# ADC_Sheet.net
KiCad netlist of a schematic drawn in Altium Designer
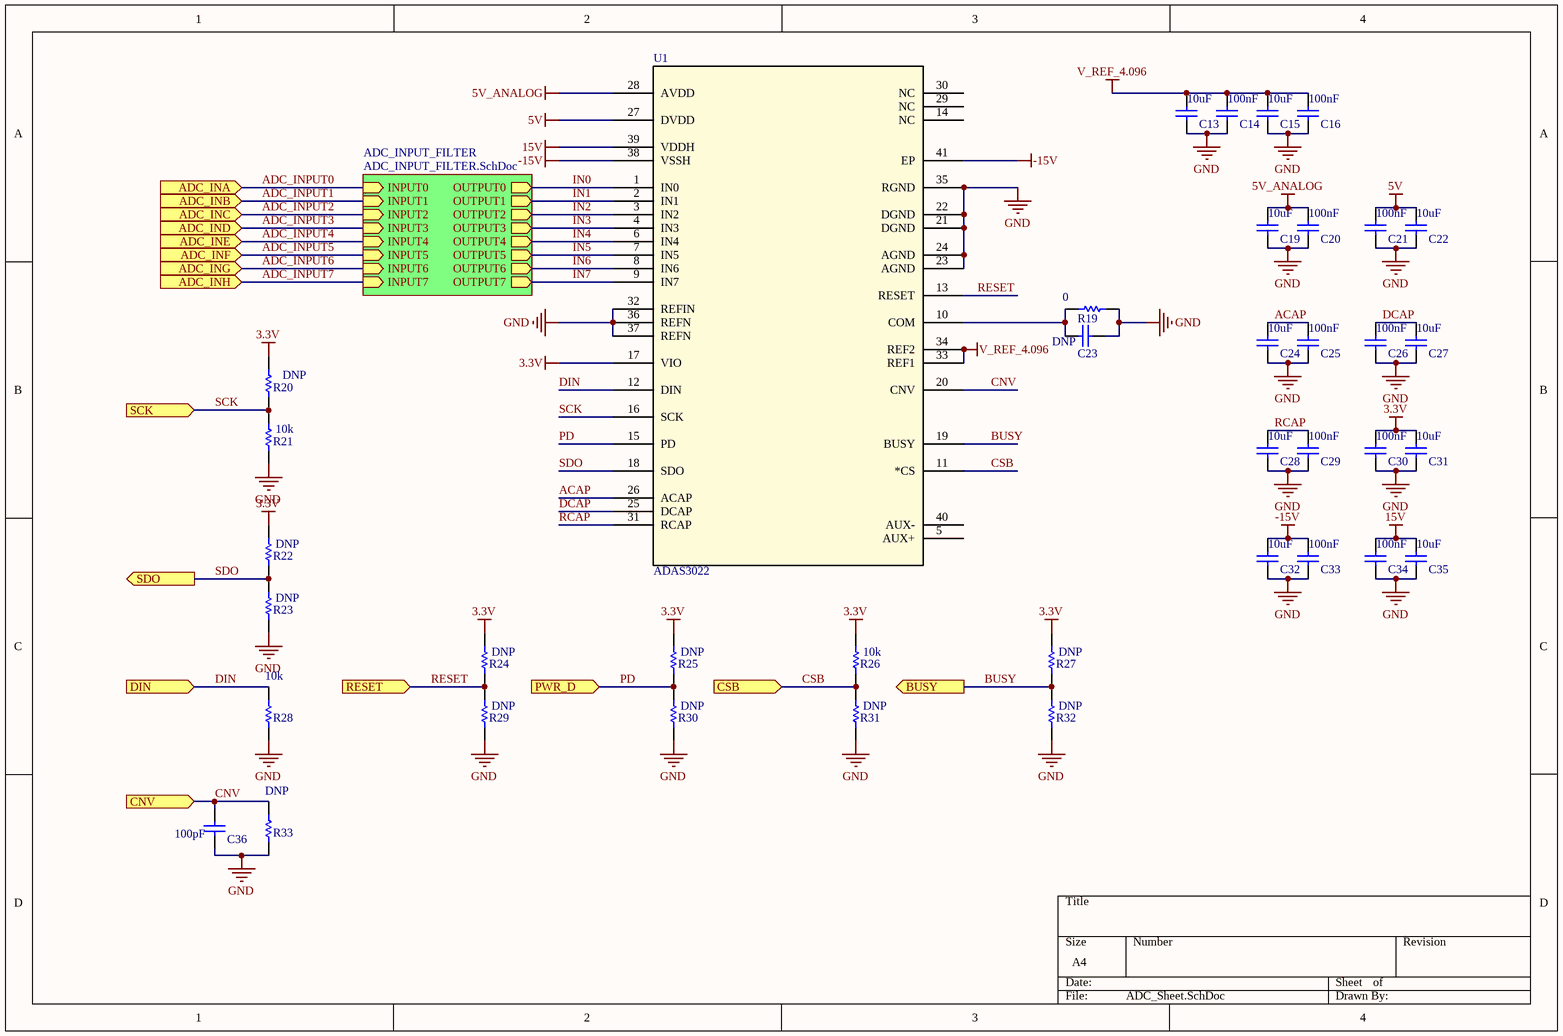
[diagram p0: ADC_Sheet.SchDoc]

(export (version "E")
  (design (tool "Eeschema 10.0.6"))
  (components
    (comp (ref "C13")
      (value "10uF")
      (footprint "CAPC0805(2012)145_L")
      (description "0805 (2012 Metric) Chip Capacitor")
      (fields (field (name "Comment") "CAP0805"))
      (libsource (lib "Altium Content Vault") (part "CMP-1590-00003-1"))
    )
    (comp (ref "C14")
      (value "100nF")
      (footprint "CAPC0402(1005)60_L")
      (description "0402 (1005 Metric) Chip Capacitor")
      (fields (field (name "Comment") "CAP0402"))
      (libsource (lib "Altium Content Vault") (part "CMP-1590-00004-1"))
    )
    (comp (ref "C15")
      (value "10uF")
      (footprint "CAPC0805(2012)145_L")
      (description "0805 (2012 Metric) Chip Capacitor")
      (fields (field (name "Comment") "CAP0805"))
      (libsource (lib "Altium Content Vault") (part "CMP-1590-00003-1"))
    )
    (comp (ref "C16")
      (value "100nF")
      (footprint "CAPC0402(1005)60_L")
      (description "0402 (1005 Metric) Chip Capacitor")
      (fields (field (name "Comment") "CAP0402"))
      (libsource (lib "Altium Content Vault") (part "CMP-1590-00004-1"))
    )
    (comp (ref "C19")
      (value "10uF")
      (footprint "CAPC0805(2012)145_L")
      (description "0805 (2012 Metric) Chip Capacitor")
      (fields (field (name "Comment") "CAP0805"))
      (libsource (lib "Altium Content Vault") (part "CMP-1590-00003-1"))
    )
    (comp (ref "C20")
      (value "100nF")
      (footprint "CAPC0402(1005)60_L")
      (description "0402 (1005 Metric) Chip Capacitor")
      (fields (field (name "Comment") "CAP0402"))
      (libsource (lib "Altium Content Vault") (part "CMP-1590-00004-1"))
    )
    (comp (ref "C21")
      (value "100nF")
      (footprint "CAPC0402(1005)60_L")
      (description "0402 (1005 Metric) Chip Capacitor")
      (fields (field (name "Comment") "CAP0402"))
      (libsource (lib "Altium Content Vault") (part "CMP-1590-00004-1"))
    )
    (comp (ref "C22")
      (value "10uF")
      (footprint "CAPC0805(2012)145_L")
      (description "0805 (2012 Metric) Chip Capacitor")
      (fields (field (name "Comment") "CAP0805"))
      (libsource (lib "Altium Content Vault") (part "CMP-1590-00003-1"))
    )
    (comp (ref "C23")
      (value "DNP")
      (footprint "CAPC0402(1005)60_L")
      (description "0402 (1005 Metric) Chip Capacitor")
      (fields (field (name "Comment") "CAP0402"))
      (libsource (lib "Altium Content Vault") (part "CMP-1590-00004-1"))
    )
    (comp (ref "C24")
      (value "10uF")
      (footprint "CAPC0805(2012)145_L")
      (description "0805 (2012 Metric) Chip Capacitor")
      (fields (field (name "Comment") "CAP0805"))
      (libsource (lib "Altium Content Vault") (part "CMP-1590-00003-1"))
    )
    (comp (ref "C25")
      (value "100nF")
      (footprint "CAPC0402(1005)60_L")
      (description "0402 (1005 Metric) Chip Capacitor")
      (fields (field (name "Comment") "CAP0402"))
      (libsource (lib "Altium Content Vault") (part "CMP-1590-00004-1"))
    )
    (comp (ref "C26")
      (value "100nF")
      (footprint "CAPC0402(1005)60_L")
      (description "0402 (1005 Metric) Chip Capacitor")
      (fields (field (name "Comment") "CAP0402"))
      (libsource (lib "Altium Content Vault") (part "CMP-1590-00004-1"))
    )
    (comp (ref "C27")
      (value "10uF")
      (footprint "CAPC0805(2012)145_L")
      (description "0805 (2012 Metric) Chip Capacitor")
      (fields (field (name "Comment") "CAP0805"))
      (libsource (lib "Altium Content Vault") (part "CMP-1590-00003-1"))
    )
    (comp (ref "C28")
      (value "10uF")
      (footprint "CAPC0805(2012)145_L")
      (description "0805 (2012 Metric) Chip Capacitor")
      (fields (field (name "Comment") "CAP0805"))
      (libsource (lib "Altium Content Vault") (part "CMP-1590-00003-1"))
    )
    (comp (ref "C29")
      (value "100nF")
      (footprint "CAPC0402(1005)60_L")
      (description "0402 (1005 Metric) Chip Capacitor")
      (fields (field (name "Comment") "CAP0402"))
      (libsource (lib "Altium Content Vault") (part "CMP-1590-00004-1"))
    )
    (comp (ref "C30")
      (value "100nF")
      (footprint "CAPC0402(1005)60_L")
      (description "0402 (1005 Metric) Chip Capacitor")
      (fields (field (name "Comment") "CAP0402"))
      (libsource (lib "Altium Content Vault") (part "CMP-1590-00004-1"))
    )
    (comp (ref "C31")
      (value "10uF")
      (footprint "CAPC0805(2012)145_L")
      (description "0805 (2012 Metric) Chip Capacitor")
      (fields (field (name "Comment") "CAP0805"))
      (libsource (lib "Altium Content Vault") (part "CMP-1590-00003-1"))
    )
    (comp (ref "C32")
      (value "10uF")
      (footprint "CAPC0805(2012)145_L")
      (description "0805 (2012 Metric) Chip Capacitor")
      (fields (field (name "Comment") "CAP0805"))
      (libsource (lib "Altium Content Vault") (part "CMP-1590-00003-1"))
    )
    (comp (ref "C33")
      (value "100nF")
      (footprint "CAPC0402(1005)60_L")
      (description "0402 (1005 Metric) Chip Capacitor")
      (fields (field (name "Comment") "CAP0402"))
      (libsource (lib "Altium Content Vault") (part "CMP-1590-00004-1"))
    )
    (comp (ref "C34")
      (value "100nF")
      (footprint "CAPC0402(1005)60_L")
      (description "0402 (1005 Metric) Chip Capacitor")
      (fields (field (name "Comment") "CAP0402"))
      (libsource (lib "Altium Content Vault") (part "CMP-1590-00004-1"))
    )
    (comp (ref "C35")
      (value "10uF")
      (footprint "CAPC0805(2012)145_L")
      (description "0805 (2012 Metric) Chip Capacitor")
      (fields (field (name "Comment") "CAP0805"))
      (libsource (lib "Altium Content Vault") (part "CMP-1590-00003-1"))
    )
    (comp (ref "C36")
      (value "100pF")
      (footprint "CAPC0402(1005)60_L")
      (description "0402 (1005 Metric) Chip Capacitor")
      (fields (field (name "Comment") "CAP0402"))
      (libsource (lib "Altium Content Vault") (part "CMP-1590-00004-1"))
    )
    (comp (ref "R19")
      (value "0")
      (footprint "RESC0402(1005)_L")
      (description "0402 (1005 Metric) Chip Resistor")
      (fields (field (name "Comment") "RES0402"))
      (libsource (lib "Altium Content Vault") (part "CMP-1591-00004-1"))
    )
    (comp (ref "R20")
      (value "DNP")
      (footprint "RESC0402(1005)_L")
      (description "0402 (1005 Metric) Chip Resistor")
      (fields (field (name "Comment") "RES0402"))
      (libsource (lib "Altium Content Vault") (part "CMP-1591-00004-1"))
    )
    (comp (ref "R21")
      (value "10k")
      (footprint "RESC0402(1005)_L")
      (description "0402 (1005 Metric) Chip Resistor")
      (fields (field (name "Comment") "RES0402"))
      (libsource (lib "Altium Content Vault") (part "CMP-1591-00004-1"))
    )
    (comp (ref "R22")
      (value "DNP")
      (footprint "RESC0402(1005)_L")
      (description "0402 (1005 Metric) Chip Resistor")
      (fields (field (name "Comment") "RES0402"))
      (libsource (lib "Altium Content Vault") (part "CMP-1591-00004-1"))
    )
    (comp (ref "R23")
      (value "DNP")
      (footprint "RESC0402(1005)_L")
      (description "0402 (1005 Metric) Chip Resistor")
      (fields (field (name "Comment") "RES0402"))
      (libsource (lib "Altium Content Vault") (part "CMP-1591-00004-1"))
    )
    (comp (ref "R24")
      (value "DNP")
      (footprint "RESC0402(1005)_L")
      (description "0402 (1005 Metric) Chip Resistor")
      (fields (field (name "Comment") "RES0402"))
      (libsource (lib "Altium Content Vault") (part "CMP-1591-00004-1"))
    )
    (comp (ref "R25")
      (value "DNP")
      (footprint "RESC0402(1005)_L")
      (description "0402 (1005 Metric) Chip Resistor")
      (fields (field (name "Comment") "RES0402"))
      (libsource (lib "Altium Content Vault") (part "CMP-1591-00004-1"))
    )
    (comp (ref "R26")
      (value "10k")
      (footprint "RESC0402(1005)_L")
      (description "0402 (1005 Metric) Chip Resistor")
      (fields (field (name "Comment") "RES0402"))
      (libsource (lib "Altium Content Vault") (part "CMP-1591-00004-1"))
    )
    (comp (ref "R27")
      (value "DNP")
      (footprint "RESC0402(1005)_L")
      (description "0402 (1005 Metric) Chip Resistor")
      (fields (field (name "Comment") "RES0402"))
      (libsource (lib "Altium Content Vault") (part "CMP-1591-00004-1"))
    )
    (comp (ref "R28")
      (value "10k")
      (footprint "RESC0402(1005)_L")
      (description "0402 (1005 Metric) Chip Resistor")
      (fields (field (name "Comment") "RES0402"))
      (libsource (lib "Altium Content Vault") (part "CMP-1591-00004-1"))
    )
    (comp (ref "R29")
      (value "DNP")
      (footprint "RESC0402(1005)_L")
      (description "0402 (1005 Metric) Chip Resistor")
      (fields (field (name "Comment") "RES0402"))
      (libsource (lib "Altium Content Vault") (part "CMP-1591-00004-1"))
    )
    (comp (ref "R30")
      (value "DNP")
      (footprint "RESC0402(1005)_L")
      (description "0402 (1005 Metric) Chip Resistor")
      (fields (field (name "Comment") "RES0402"))
      (libsource (lib "Altium Content Vault") (part "CMP-1591-00004-1"))
    )
    (comp (ref "R31")
      (value "DNP")
      (footprint "RESC0402(1005)_L")
      (description "0402 (1005 Metric) Chip Resistor")
      (fields (field (name "Comment") "RES0402"))
      (libsource (lib "Altium Content Vault") (part "CMP-1591-00004-1"))
    )
    (comp (ref "R32")
      (value "DNP")
      (footprint "RESC0402(1005)_L")
      (description "0402 (1005 Metric) Chip Resistor")
      (fields (field (name "Comment") "RES0402"))
      (libsource (lib "Altium Content Vault") (part "CMP-1591-00004-1"))
    )
    (comp (ref "R33")
      (value "DNP")
      (footprint "RESC0402(1005)_L")
      (description "0402 (1005 Metric) Chip Resistor")
      (fields (field (name "Comment") "RES0402"))
      (libsource (lib "Altium Content Vault") (part "CMP-1591-00004-1"))
    )
    (comp (ref "U1")
      (value "ADAS3022")
      (footprint "CP_40_7")
      (fields
        (field (name "MANUFACTURER") "Analog Devices Inc.")
        (field (name "MANUFACTURER PART NUMBER") "ADAS3022BCPZ")
      )
      (libsource (lib "DAQ_Replacement") (part "ADAS3022"))
    )
  )
  (nets
    (net (code "1") (name "-15V") (class "Default")
      (node (ref "C32") (pin "2") (pinfunction "2_2") (pintype "passive"))
      (node (ref "C33") (pin "1") (pinfunction "1_1") (pintype "passive"))
      (node (ref "U1") (pin "38") (pinfunction "VSSH_38") (pintype "passive"))
      (node (ref "U1") (pin "41") (pinfunction "EP_41") (pintype "passive"))
    )
    (net (code "2") (name "/ACAP") (class "Default")
      (node (ref "C24") (pin "2") (pinfunction "2_2") (pintype "passive"))
      (node (ref "C25") (pin "1") (pinfunction "1_1") (pintype "passive"))
      (node (ref "U1") (pin "26") (pinfunction "ACAP_26") (pintype "passive"))
    )
    (net (code "11") (name "/BUSY") (class "Default")
      (node (ref "R27") (pin "2") (pinfunction "2_2") (pintype "passive"))
      (node (ref "R32") (pin "1") (pinfunction "1_1") (pintype "passive"))
      (node (ref "U1") (pin "19") (pinfunction "BUSY_19") (pintype "passive"))
    )
    (net (code "12") (name "/CNV") (class "Default")
      (node (ref "C36") (pin "1") (pinfunction "1_1") (pintype "passive"))
      (node (ref "R33") (pin "1") (pinfunction "1_1") (pintype "passive"))
      (node (ref "U1") (pin "20") (pinfunction "CNV_20") (pintype "passive"))
    )
    (net (code "13") (name "/CSB") (class "Default")
      (node (ref "R26") (pin "2") (pinfunction "2_2") (pintype "passive"))
      (node (ref "R31") (pin "1") (pinfunction "1_1") (pintype "passive"))
      (node (ref "U1") (pin "11") (pinfunction "*CS_11") (pintype "passive"))
    )
    (net (code "14") (name "/DCAP") (class "Default")
      (node (ref "C26") (pin "1") (pinfunction "1_1") (pintype "passive"))
      (node (ref "C27") (pin "2") (pinfunction "2_2") (pintype "passive"))
      (node (ref "U1") (pin "25") (pinfunction "DCAP_25") (pintype "passive"))
    )
    (net (code "15") (name "/DIN") (class "Default")
      (node (ref "R28") (pin "1") (pinfunction "1_1") (pintype "passive"))
      (node (ref "U1") (pin "12") (pinfunction "DIN_12") (pintype "passive"))
    )
    (net (code "16") (name "/IN0") (class "Default")
      (node (ref "U1") (pin "1") (pinfunction "IN0_1") (pintype "passive"))
    )
    (net (code "17") (name "/IN1") (class "Default")
      (node (ref "U1") (pin "2") (pinfunction "IN1_2") (pintype "passive"))
    )
    (net (code "18") (name "/IN2") (class "Default")
      (node (ref "U1") (pin "3") (pinfunction "IN2_3") (pintype "passive"))
    )
    (net (code "19") (name "/IN3") (class "Default")
      (node (ref "U1") (pin "4") (pinfunction "IN3_4") (pintype "passive"))
    )
    (net (code "20") (name "/IN4") (class "Default")
      (node (ref "U1") (pin "6") (pinfunction "IN4_6") (pintype "passive"))
    )
    (net (code "21") (name "/IN5") (class "Default")
      (node (ref "U1") (pin "7") (pinfunction "IN5_7") (pintype "passive"))
    )
    (net (code "22") (name "/IN6") (class "Default")
      (node (ref "U1") (pin "8") (pinfunction "IN6_8") (pintype "passive"))
    )
    (net (code "23") (name "/IN7") (class "Default")
      (node (ref "U1") (pin "9") (pinfunction "IN7_9") (pintype "passive"))
    )
    (net (code "24") (name "/PD") (class "Default")
      (node (ref "R25") (pin "2") (pinfunction "2_2") (pintype "passive"))
      (node (ref "R30") (pin "1") (pinfunction "1_1") (pintype "passive"))
      (node (ref "U1") (pin "15") (pinfunction "PD_15") (pintype "passive"))
    )
    (net (code "25") (name "/RCAP") (class "Default")
      (node (ref "C28") (pin "2") (pinfunction "2_2") (pintype "passive"))
      (node (ref "C29") (pin "1") (pinfunction "1_1") (pintype "passive"))
      (node (ref "U1") (pin "31") (pinfunction "RCAP_31") (pintype "passive"))
    )
    (net (code "26") (name "/RESET") (class "Default")
      (node (ref "R24") (pin "2") (pinfunction "2_2") (pintype "passive"))
      (node (ref "R29") (pin "1") (pinfunction "1_1") (pintype "passive"))
      (node (ref "U1") (pin "13") (pinfunction "RESET_13") (pintype "passive"))
    )
    (net (code "27") (name "/SCK") (class "Default")
      (node (ref "R20") (pin "2") (pinfunction "2_2") (pintype "passive"))
      (node (ref "R21") (pin "1") (pinfunction "1_1") (pintype "passive"))
      (node (ref "U1") (pin "16") (pinfunction "SCK_16") (pintype "passive"))
    )
    (net (code "28") (name "/SDO") (class "Default")
      (node (ref "R22") (pin "2") (pinfunction "2_2") (pintype "passive"))
      (node (ref "R23") (pin "1") (pinfunction "1_1") (pintype "passive"))
      (node (ref "U1") (pin "18") (pinfunction "SDO_18") (pintype "passive"))
    )
    (net (code "29") (name "3.3V") (class "Default")
      (node (ref "C30") (pin "1") (pinfunction "1_1") (pintype "passive"))
      (node (ref "C31") (pin "2") (pinfunction "2_2") (pintype "passive"))
      (node (ref "R20") (pin "1") (pinfunction "1_1") (pintype "passive"))
      (node (ref "R22") (pin "1") (pinfunction "1_1") (pintype "passive"))
      (node (ref "R24") (pin "1") (pinfunction "1_1") (pintype "passive"))
      (node (ref "R25") (pin "1") (pinfunction "1_1") (pintype "passive"))
      (node (ref "R26") (pin "1") (pinfunction "1_1") (pintype "passive"))
      (node (ref "R27") (pin "1") (pinfunction "1_1") (pintype "passive"))
      (node (ref "U1") (pin "17") (pinfunction "VIO_17") (pintype "passive"))
    )
    (net (code "30") (name "5V") (class "Default")
      (node (ref "C21") (pin "1") (pinfunction "1_1") (pintype "passive"))
      (node (ref "C22") (pin "2") (pinfunction "2_2") (pintype "passive"))
      (node (ref "U1") (pin "27") (pinfunction "DVDD_27") (pintype "passive"))
    )
    (net (code "31") (name "5V_ANALOG") (class "Default")
      (node (ref "C19") (pin "2") (pinfunction "2_2") (pintype "passive"))
      (node (ref "C20") (pin "1") (pinfunction "1_1") (pintype "passive"))
      (node (ref "U1") (pin "28") (pinfunction "AVDD_28") (pintype "passive"))
    )
    (net (code "32") (name "15V") (class "Default")
      (node (ref "C34") (pin "1") (pinfunction "1_1") (pintype "passive"))
      (node (ref "C35") (pin "2") (pinfunction "2_2") (pintype "passive"))
      (node (ref "U1") (pin "39") (pinfunction "VDDH_39") (pintype "passive"))
    )
    (net (code "33") (name "GND") (class "Default")
      (node (ref "C13") (pin "1") (pinfunction "1_1") (pintype "passive"))
      (node (ref "C14") (pin "2") (pinfunction "2_2") (pintype "passive"))
      (node (ref "C15") (pin "1") (pinfunction "1_1") (pintype "passive"))
      (node (ref "C16") (pin "2") (pinfunction "2_2") (pintype "passive"))
      (node (ref "C19") (pin "1") (pinfunction "1_1") (pintype "passive"))
      (node (ref "C20") (pin "2") (pinfunction "2_2") (pintype "passive"))
      (node (ref "C21") (pin "2") (pinfunction "2_2") (pintype "passive"))
      (node (ref "C22") (pin "1") (pinfunction "1_1") (pintype "passive"))
      (node (ref "C23") (pin "1") (pinfunction "1_1") (pintype "passive"))
      (node (ref "C24") (pin "1") (pinfunction "1_1") (pintype "passive"))
      (node (ref "C25") (pin "2") (pinfunction "2_2") (pintype "passive"))
      (node (ref "C26") (pin "2") (pinfunction "2_2") (pintype "passive"))
      (node (ref "C27") (pin "1") (pinfunction "1_1") (pintype "passive"))
      (node (ref "C28") (pin "1") (pinfunction "1_1") (pintype "passive"))
      (node (ref "C29") (pin "2") (pinfunction "2_2") (pintype "passive"))
      (node (ref "C30") (pin "2") (pinfunction "2_2") (pintype "passive"))
      (node (ref "C31") (pin "1") (pinfunction "1_1") (pintype "passive"))
      (node (ref "C32") (pin "1") (pinfunction "1_1") (pintype "passive"))
      (node (ref "C33") (pin "2") (pinfunction "2_2") (pintype "passive"))
      (node (ref "C34") (pin "2") (pinfunction "2_2") (pintype "passive"))
      (node (ref "C35") (pin "1") (pinfunction "1_1") (pintype "passive"))
      (node (ref "C36") (pin "2") (pinfunction "2_2") (pintype "passive"))
      (node (ref "R19") (pin "1") (pinfunction "1_1") (pintype "passive"))
      (node (ref "R21") (pin "2") (pinfunction "2_2") (pintype "passive"))
      (node (ref "R23") (pin "2") (pinfunction "2_2") (pintype "passive"))
      (node (ref "R28") (pin "2") (pinfunction "2_2") (pintype "passive"))
      (node (ref "R29") (pin "2") (pinfunction "2_2") (pintype "passive"))
      (node (ref "R30") (pin "2") (pinfunction "2_2") (pintype "passive"))
      (node (ref "R31") (pin "2") (pinfunction "2_2") (pintype "passive"))
      (node (ref "R32") (pin "2") (pinfunction "2_2") (pintype "passive"))
      (node (ref "R33") (pin "2") (pinfunction "2_2") (pintype "passive"))
      (node (ref "U1") (pin "21") (pinfunction "DGND_21") (pintype "passive"))
      (node (ref "U1") (pin "22") (pinfunction "DGND_22") (pintype "passive"))
      (node (ref "U1") (pin "23") (pinfunction "AGND_23") (pintype "passive"))
      (node (ref "U1") (pin "24") (pinfunction "AGND_24") (pintype "passive"))
      (node (ref "U1") (pin "32") (pinfunction "REFIN_32") (pintype "passive"))
      (node (ref "U1") (pin "35") (pinfunction "RGND_35") (pintype "passive"))
      (node (ref "U1") (pin "36") (pinfunction "REFN_36") (pintype "passive"))
      (node (ref "U1") (pin "37") (pinfunction "REFN_37") (pintype "passive"))
    )
    (net (code "34") (name "Net-(U1-COM)") (class "Default")
      (node (ref "C23") (pin "2") (pinfunction "2_2") (pintype "passive"))
      (node (ref "R19") (pin "2") (pinfunction "2_2") (pintype "passive"))
      (node (ref "U1") (pin "10") (pinfunction "COM_10") (pintype "passive"))
    )
    (net (code "35") (name "V_REF_4.096") (class "Default")
      (node (ref "C13") (pin "2") (pinfunction "2_2") (pintype "passive"))
      (node (ref "C14") (pin "1") (pinfunction "1_1") (pintype "passive"))
      (node (ref "C15") (pin "2") (pinfunction "2_2") (pintype "passive"))
      (node (ref "C16") (pin "1") (pinfunction "1_1") (pintype "passive"))
      (node (ref "U1") (pin "33") (pinfunction "REF1_33") (pintype "passive"))
      (node (ref "U1") (pin "34") (pinfunction "REF2_34") (pintype "passive"))
    )
    (net (code "36") (name "unconnected-(U1-AUX+-Pad5)") (class "Default")
      (node (ref "U1") (pin "5") (pinfunction "AUX+_5") (pintype "passive"))
    )
    (net (code "37") (name "unconnected-(U1-AUX--Pad40)") (class "Default")
      (node (ref "U1") (pin "40") (pinfunction "AUX-_40") (pintype "passive"))
    )
    (net (code "38") (name "unconnected-(U1-NC-Pad14)") (class "Default")
      (node (ref "U1") (pin "14") (pinfunction "NC_14") (pintype "passive"))
    )
    (net (code "39") (name "unconnected-(U1-NC-Pad29)") (class "Default")
      (node (ref "U1") (pin "29") (pinfunction "NC_29") (pintype "passive"))
    )
    (net (code "40") (name "unconnected-(U1-NC-Pad30)") (class "Default")
      (node (ref "U1") (pin "30") (pinfunction "NC_30") (pintype "passive"))
    )
  )
)
